# MotorDriver.net
KiCad netlist of a schematic drawn in Altium Designer
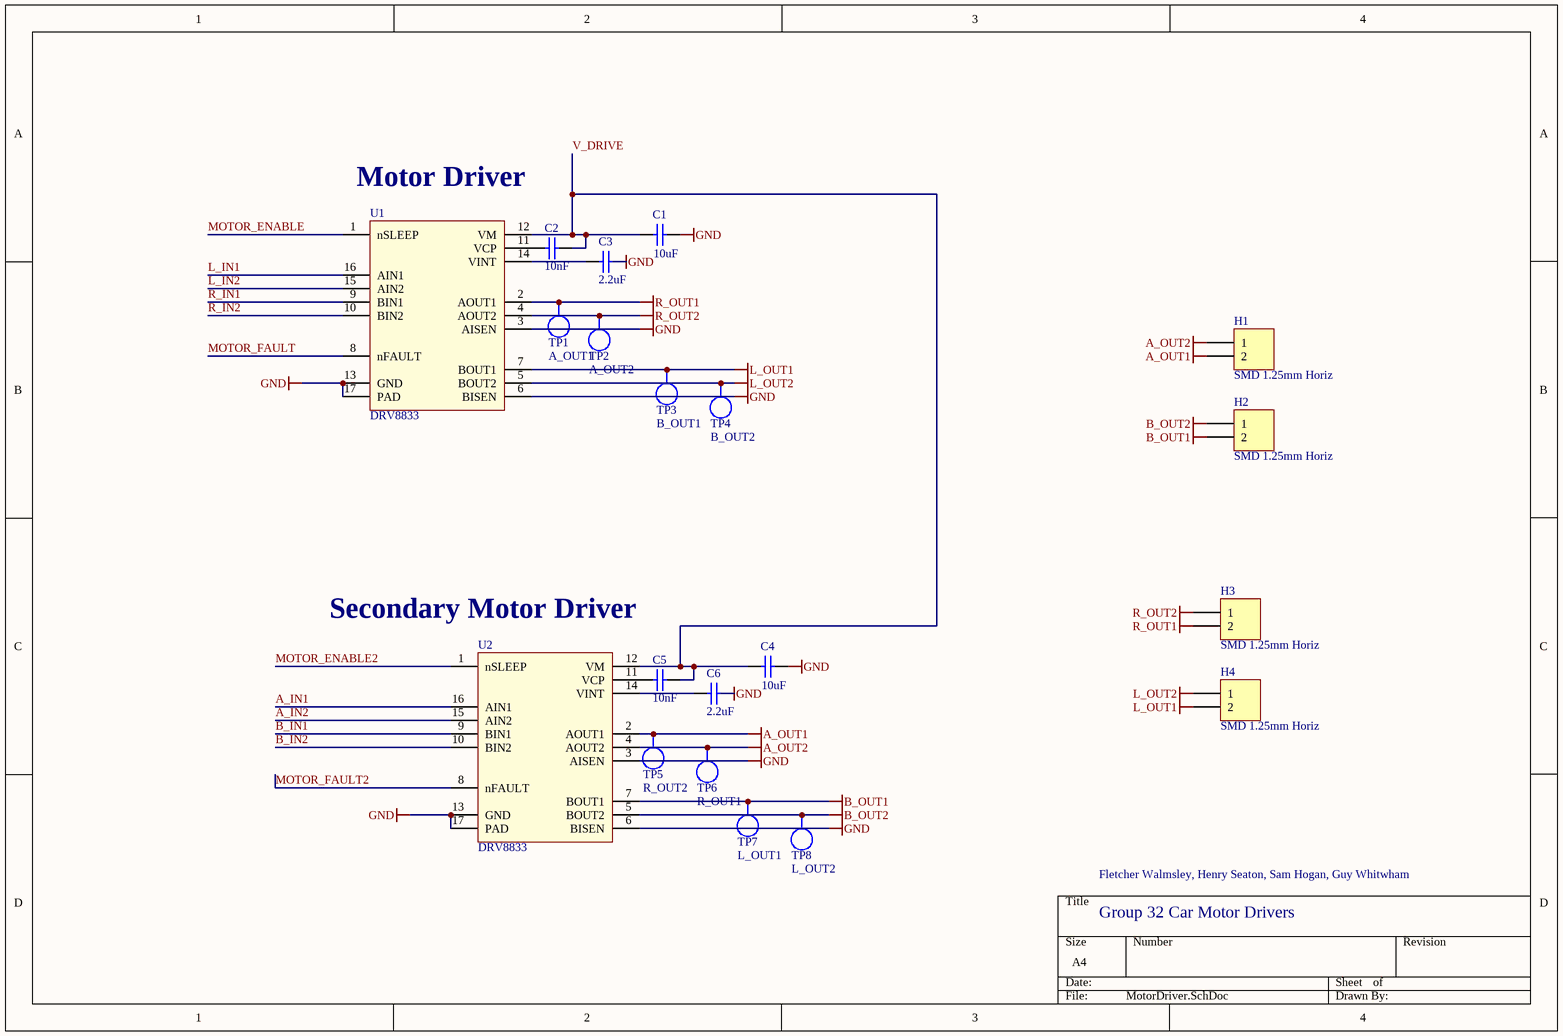
[diagram p0: MotorDriver.SchDoc]

(export (version "E")
  (design (tool "Eeschema 10.0.6"))
  (components
    (comp (ref "C1")
      (value "10uF")
      (footprint "CAPC2012L")
      (description "CAP CER 10uF X5R 16V 0805")
      (fields
        (field (name "MANUFACTURER") "Samsung Electro-Mechanics")
        (field (name "MANUFACTURER PART NUMBER") "CL21A106KOQNNWE")
      )
      (libsource (lib "ENCE461AD19_19V2") (part "CC_10uF_16V_0805"))
    )
    (comp (ref "C2")
      (value "10nF")
      (footprint "CAPC1608L")
      (description "CAP CER 10nF X7R +-10% 50V 0603")
      (libsource (lib "ECE AD19Components_19V1") (part "CC_10nF_0603"))
    )
    (comp (ref "C3")
      (value "2.2uF")
      (footprint "CAPC1608L")
      (description "CAP CER 2.2uF X5R +-20% 10V 0603")
      (libsource (lib "ECE AD19Components_19V1") (part "CC_2.2uF_0603"))
    )
    (comp (ref "C4")
      (value "10uF")
      (footprint "CAPC2012L")
      (description "CAP CER 10uF X5R 16V 0805")
      (fields
        (field (name "MANUFACTURER") "Samsung Electro-Mechanics")
        (field (name "MANUFACTURER PART NUMBER") "CL21A106KOQNNWE")
      )
      (libsource (lib "ENCE461AD19_19V2") (part "CC_10uF_16V_0805"))
    )
    (comp (ref "C5")
      (value "10nF")
      (footprint "CAPC1608L")
      (description "CAP CER 10nF X7R +-10% 50V 0603")
      (libsource (lib "ECE AD19Components_19V1") (part "CC_10nF_0603"))
    )
    (comp (ref "C6")
      (value "2.2uF")
      (footprint "CAPC1608L")
      (description "CAP CER 2.2uF X5R +-20% 10V 0603")
      (libsource (lib "ECE AD19Components_19V1") (part "CC_2.2uF_0603"))
    )
    (comp (ref "H1")
      (value "SMD 1.25mm Horiz")
      (footprint "SD-53261-0219")
      (description "Header_Horiz_2Pos_1.25mm_125V@1A_SMT")
      (fields (field (name "MANUFACTURER") "MOLEX") (field (name "MANUFACTURER PART NUMBER") "53261-0271"))
      (libsource (lib "ECE AD19Components_19V1") (part "JB_53261-02"))
    )
    (comp (ref "H2")
      (value "SMD 1.25mm Horiz")
      (footprint "SD-53261-0219")
      (description "Header_Horiz_2Pos_1.25mm_125V@1A_SMT")
      (fields (field (name "MANUFACTURER") "MOLEX") (field (name "MANUFACTURER PART NUMBER") "53261-0271"))
      (libsource (lib "ECE AD19Components_19V1") (part "JB_53261-02"))
    )
    (comp (ref "H3")
      (value "SMD 1.25mm Horiz")
      (footprint "SD-53261-0219")
      (description "Header_Horiz_2Pos_1.25mm_125V@1A_SMT")
      (fields (field (name "MANUFACTURER") "MOLEX") (field (name "MANUFACTURER PART NUMBER") "53261-0271"))
      (libsource (lib "ECE AD19Components_19V1") (part "JB_53261-02"))
    )
    (comp (ref "H4")
      (value "SMD 1.25mm Horiz")
      (footprint "SD-53261-0219")
      (description "Header_Horiz_2Pos_1.25mm_125V@1A_SMT")
      (fields (field (name "MANUFACTURER") "MOLEX") (field (name "MANUFACTURER PART NUMBER") "53261-0271"))
      (libsource (lib "ECE AD19Components_19V1") (part "JB_53261-02"))
    )
    (comp (ref "TP1")
      (value "A_OUT1")
      (footprint "TP_1206")
      (description "Test-Point 3.3x1.6x2.1mm SMD")
      (fields
        (field (name "MANUFACTURER") "Harwin Inc")
        (field (name "MANUFACTURER PART NUMBER") "S1751-46R")
      )
      (libsource (lib "ECE AD19Components_19V1") (part "TP_1206"))
    )
    (comp (ref "TP2")
      (value "A_OUT2")
      (footprint "TP_1206")
      (description "Test-Point 3.3x1.6x2.1mm SMD")
      (fields
        (field (name "MANUFACTURER") "Harwin Inc")
        (field (name "MANUFACTURER PART NUMBER") "S1751-46R")
      )
      (libsource (lib "ECE AD19Components_19V1") (part "TP_1206"))
    )
    (comp (ref "TP3")
      (value "B_OUT1")
      (footprint "TP_1206")
      (description "Test-Point 3.3x1.6x2.1mm SMD")
      (fields
        (field (name "MANUFACTURER") "Harwin Inc")
        (field (name "MANUFACTURER PART NUMBER") "S1751-46R")
      )
      (libsource (lib "ECE AD19Components_19V1") (part "TP_1206"))
    )
    (comp (ref "TP4")
      (value "B_OUT2")
      (footprint "TP_1206")
      (description "Test-Point 3.3x1.6x2.1mm SMD")
      (fields
        (field (name "MANUFACTURER") "Harwin Inc")
        (field (name "MANUFACTURER PART NUMBER") "S1751-46R")
      )
      (libsource (lib "ECE AD19Components_19V1") (part "TP_1206"))
    )
    (comp (ref "TP5")
      (value "R_OUT2")
      (footprint "TP_1206")
      (description "Test-Point 3.3x1.6x2.1mm SMD")
      (fields
        (field (name "MANUFACTURER") "Harwin Inc")
        (field (name "MANUFACTURER PART NUMBER") "S1751-46R")
      )
      (libsource (lib "ECE AD19Components_19V1") (part "TP_1206"))
    )
    (comp (ref "TP6")
      (value "R_OUT1")
      (footprint "TP_1206")
      (description "Test-Point 3.3x1.6x2.1mm SMD")
      (fields
        (field (name "MANUFACTURER") "Harwin Inc")
        (field (name "MANUFACTURER PART NUMBER") "S1751-46R")
      )
      (libsource (lib "ECE AD19Components_19V1") (part "TP_1206"))
    )
    (comp (ref "TP7")
      (value "L_OUT1")
      (footprint "TP_1206")
      (description "Test-Point 3.3x1.6x2.1mm SMD")
      (fields
        (field (name "MANUFACTURER") "Harwin Inc")
        (field (name "MANUFACTURER PART NUMBER") "S1751-46R")
      )
      (libsource (lib "ECE AD19Components_19V1") (part "TP_1206"))
    )
    (comp (ref "TP8")
      (value "L_OUT2")
      (footprint "TP_1206")
      (description "Test-Point 3.3x1.6x2.1mm SMD")
      (fields
        (field (name "MANUFACTURER") "Harwin Inc")
        (field (name "MANUFACTURER PART NUMBER") "S1751-46R")
      )
      (libsource (lib "ECE AD19Components_19V1") (part "TP_1206"))
    )
    (comp (ref "U1")
      (value "DRV8833")
      (footprint "HTSOP16")
      (description "Dual H-Bridge Motor Driver 1.5A")
      (libsource (lib "ENCE461AD19_19V2") (part "DRV8833"))
    )
    (comp (ref "U2")
      (value "DRV8833")
      (footprint "HTSOP16")
      (description "Dual H-Bridge Motor Driver 1.5A")
      (libsource (lib "ENCE461AD19_19V2") (part "DRV8833"))
    )
  )
  (nets
    (net (code "1") (name "/A_IN1") (class "Default")
      (node (ref "U2") (pin "16") (pinfunction "AIN1_16") (pintype "passive"))
    )
    (net (code "2") (name "/A_IN2") (class "Default")
      (node (ref "U2") (pin "15") (pinfunction "AIN2_15") (pintype "passive"))
    )
    (net (code "3") (name "/B_IN1") (class "Default")
      (node (ref "U2") (pin "9") (pinfunction "BIN1_9") (pintype "passive"))
    )
    (net (code "4") (name "/B_IN2") (class "Default")
      (node (ref "U2") (pin "10") (pinfunction "BIN2_10") (pintype "passive"))
    )
    (net (code "5") (name "/L_IN1") (class "Default")
      (node (ref "U1") (pin "16") (pinfunction "AIN1_16") (pintype "passive"))
    )
    (net (code "6") (name "/L_IN2") (class "Default")
      (node (ref "U1") (pin "15") (pinfunction "AIN2_15") (pintype "passive"))
    )
    (net (code "7") (name "/MOTOR_ENABLE") (class "Default")
      (node (ref "U1") (pin "1") (pinfunction "nSLEEP_1") (pintype "passive"))
    )
    (net (code "8") (name "/MOTOR_ENABLE2") (class "Default")
      (node (ref "U2") (pin "1") (pinfunction "nSLEEP_1") (pintype "passive"))
    )
    (net (code "9") (name "/MOTOR_FAULT") (class "Default")
      (node (ref "U1") (pin "8") (pinfunction "nFAULT_8") (pintype "passive"))
    )
    (net (code "10") (name "/MOTOR_FAULT2") (class "Default")
      (node (ref "U2") (pin "8") (pinfunction "nFAULT_8") (pintype "passive"))
    )
    (net (code "11") (name "/R_IN1") (class "Default")
      (node (ref "U1") (pin "9") (pinfunction "BIN1_9") (pintype "passive"))
    )
    (net (code "12") (name "/R_IN2") (class "Default")
      (node (ref "U1") (pin "10") (pinfunction "BIN2_10") (pintype "passive"))
    )
    (net (code "13") (name "/V_DRIVE") (class "Default")
      (node (ref "C1") (pin "2") (pinfunction "2_2") (pintype "passive"))
      (node (ref "C2") (pin "2") (pinfunction "2_2") (pintype "passive"))
      (node (ref "C4") (pin "2") (pinfunction "2_2") (pintype "passive"))
      (node (ref "C5") (pin "2") (pinfunction "2_2") (pintype "passive"))
      (node (ref "U1") (pin "12") (pinfunction "VM_12") (pintype "passive"))
      (node (ref "U2") (pin "12") (pinfunction "VM_12") (pintype "passive"))
    )
    (net (code "14") (name "A_OUT1") (class "Default")
      (node (ref "H1") (pin "2") (pinfunction "2_2") (pintype "passive"))
      (node (ref "TP5") (pin "1") (pinfunction "1_1") (pintype "passive"))
      (node (ref "U2") (pin "2") (pinfunction "AOUT1_2") (pintype "passive"))
    )
    (net (code "15") (name "A_OUT2") (class "Default")
      (node (ref "H1") (pin "1") (pinfunction "1_1") (pintype "passive"))
      (node (ref "TP6") (pin "1") (pinfunction "1_1") (pintype "passive"))
      (node (ref "U2") (pin "4") (pinfunction "AOUT2_4") (pintype "passive"))
    )
    (net (code "16") (name "B_OUT1") (class "Default")
      (node (ref "H2") (pin "2") (pinfunction "2_2") (pintype "passive"))
      (node (ref "TP7") (pin "1") (pinfunction "1_1") (pintype "passive"))
      (node (ref "U2") (pin "7") (pinfunction "BOUT1_7") (pintype "passive"))
    )
    (net (code "17") (name "B_OUT2") (class "Default")
      (node (ref "H2") (pin "1") (pinfunction "1_1") (pintype "passive"))
      (node (ref "TP8") (pin "1") (pinfunction "1_1") (pintype "passive"))
      (node (ref "U2") (pin "5") (pinfunction "BOUT2_5") (pintype "passive"))
    )
    (net (code "18") (name "GND") (class "Default")
      (node (ref "C1") (pin "1") (pinfunction "1_1") (pintype "passive"))
      (node (ref "C3") (pin "1") (pinfunction "1_1") (pintype "passive"))
      (node (ref "C4") (pin "1") (pinfunction "1_1") (pintype "passive"))
      (node (ref "C6") (pin "1") (pinfunction "1_1") (pintype "passive"))
      (node (ref "U1") (pin "13") (pinfunction "GND_13") (pintype "passive"))
      (node (ref "U1") (pin "17") (pinfunction "PAD_17") (pintype "passive"))
      (node (ref "U1") (pin "3") (pinfunction "AISEN_3") (pintype "passive"))
      (node (ref "U1") (pin "6") (pinfunction "BISEN_6") (pintype "passive"))
      (node (ref "U2") (pin "13") (pinfunction "GND_13") (pintype "passive"))
      (node (ref "U2") (pin "17") (pinfunction "PAD_17") (pintype "passive"))
      (node (ref "U2") (pin "3") (pinfunction "AISEN_3") (pintype "passive"))
      (node (ref "U2") (pin "6") (pinfunction "BISEN_6") (pintype "passive"))
    )
    (net (code "19") (name "L_OUT1") (class "Default")
      (node (ref "H4") (pin "2") (pinfunction "2_2") (pintype "passive"))
      (node (ref "TP3") (pin "1") (pinfunction "1_1") (pintype "passive"))
      (node (ref "U1") (pin "7") (pinfunction "BOUT1_7") (pintype "passive"))
    )
    (net (code "20") (name "L_OUT2") (class "Default")
      (node (ref "H4") (pin "1") (pinfunction "1_1") (pintype "passive"))
      (node (ref "TP4") (pin "1") (pinfunction "1_1") (pintype "passive"))
      (node (ref "U1") (pin "5") (pinfunction "BOUT2_5") (pintype "passive"))
    )
    (net (code "21") (name "Net-(U1-VCP)") (class "Default")
      (node (ref "C2") (pin "1") (pinfunction "1_1") (pintype "passive"))
      (node (ref "U1") (pin "11") (pinfunction "VCP_11") (pintype "passive"))
    )
    (net (code "22") (name "Net-(U1-VINT)") (class "Default")
      (node (ref "C3") (pin "2") (pinfunction "2_2") (pintype "passive"))
      (node (ref "U1") (pin "14") (pinfunction "VINT_14") (pintype "passive"))
    )
    (net (code "23") (name "Net-(U2-VCP)") (class "Default")
      (node (ref "C5") (pin "1") (pinfunction "1_1") (pintype "passive"))
      (node (ref "U2") (pin "11") (pinfunction "VCP_11") (pintype "passive"))
    )
    (net (code "24") (name "Net-(U2-VINT)") (class "Default")
      (node (ref "C6") (pin "2") (pinfunction "2_2") (pintype "passive"))
      (node (ref "U2") (pin "14") (pinfunction "VINT_14") (pintype "passive"))
    )
    (net (code "25") (name "R_OUT1") (class "Default")
      (node (ref "H3") (pin "2") (pinfunction "2_2") (pintype "passive"))
      (node (ref "TP1") (pin "1") (pinfunction "1_1") (pintype "passive"))
      (node (ref "U1") (pin "2") (pinfunction "AOUT1_2") (pintype "passive"))
    )
    (net (code "26") (name "R_OUT2") (class "Default")
      (node (ref "H3") (pin "1") (pinfunction "1_1") (pintype "passive"))
      (node (ref "TP2") (pin "1") (pinfunction "1_1") (pintype "passive"))
      (node (ref "U1") (pin "4") (pinfunction "AOUT2_4") (pintype "passive"))
    )
  )
)
